# Schematic.net
KiCad netlist of a schematic drawn in Altium Designer
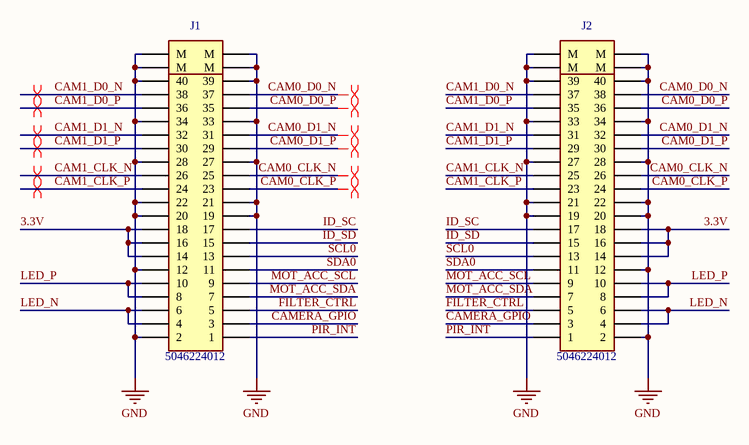
[diagram p0: Schematic.SchDoc]

(export (version "E")
  (design (tool "Eeschema 10.0.6"))
  (components
    (comp (ref "J1")
      (value "5046224012")
      (footprint "MOLEX 5046224012")
      (description "SMT 2x20 0.35mm Straight 50V 0.3A")
      (fields (field (name "02 MPN") "5046224012"))
      (libsource (lib "MS_Altium_Lib") (part "CONNECTOR 2X22 4MNT ODDEVEN"))
    )
    (comp (ref "J2")
      (value "5046224012")
      (footprint "MOLEX 5046224012")
      (description "SMT 2x20 0.35mm Straight 50V 0.3A")
      (fields (field (name "02 MPN") "5046224012"))
      (libsource (lib "") (part "CONNECTOR 2X22 4MNT ODDEVEN_1"))
    )
  )
  (nets
    (net (code "1") (name "/3.3V") (class "Default")
      (node (ref "J1") (pin "14") (pinfunction "14_14") (pintype "passive"))
      (node (ref "J1") (pin "16") (pinfunction "16_16") (pintype "passive"))
      (node (ref "J1") (pin "18") (pinfunction "18_18") (pintype "passive"))
      (node (ref "J2") (pin "14") (pinfunction "14_14") (pintype "passive"))
      (node (ref "J2") (pin "16") (pinfunction "16_16") (pintype "passive"))
      (node (ref "J2") (pin "18") (pinfunction "18_18") (pintype "passive"))
    )
    (net (code "2") (name "/CAM0_CLK_N") (class "Default")
      (node (ref "J1") (pin "25") (pinfunction "25_25") (pintype "passive"))
      (node (ref "J2") (pin "26") (pinfunction "26_26") (pintype "passive"))
    )
    (net (code "3") (name "/CAM0_CLK_P") (class "Default")
      (node (ref "J1") (pin "23") (pinfunction "23_23") (pintype "passive"))
      (node (ref "J2") (pin "24") (pinfunction "24_24") (pintype "passive"))
    )
    (net (code "4") (name "/CAM0_D0_N") (class "Default")
      (node (ref "J1") (pin "37") (pinfunction "37_37") (pintype "passive"))
      (node (ref "J2") (pin "38") (pinfunction "38_38") (pintype "passive"))
    )
    (net (code "5") (name "/CAM0_D0_P") (class "Default")
      (node (ref "J1") (pin "35") (pinfunction "35_35") (pintype "passive"))
      (node (ref "J2") (pin "36") (pinfunction "36_36") (pintype "passive"))
    )
    (net (code "6") (name "/CAM0_D1_N") (class "Default")
      (node (ref "J1") (pin "31") (pinfunction "31_31") (pintype "passive"))
      (node (ref "J2") (pin "32") (pinfunction "32_32") (pintype "passive"))
    )
    (net (code "7") (name "/CAM0_D1_P") (class "Default")
      (node (ref "J1") (pin "29") (pinfunction "29_29") (pintype "passive"))
      (node (ref "J2") (pin "30") (pinfunction "30_30") (pintype "passive"))
    )
    (net (code "8") (name "/CAM1_CLK_N") (class "Default")
      (node (ref "J1") (pin "26") (pinfunction "26_26") (pintype "passive"))
      (node (ref "J2") (pin "25") (pinfunction "25_25") (pintype "passive"))
    )
    (net (code "9") (name "/CAM1_CLK_P") (class "Default")
      (node (ref "J1") (pin "24") (pinfunction "24_24") (pintype "passive"))
      (node (ref "J2") (pin "23") (pinfunction "23_23") (pintype "passive"))
    )
    (net (code "10") (name "/CAM1_D0_N") (class "Default")
      (node (ref "J1") (pin "38") (pinfunction "38_38") (pintype "passive"))
      (node (ref "J2") (pin "37") (pinfunction "37_37") (pintype "passive"))
    )
    (net (code "11") (name "/CAM1_D0_P") (class "Default")
      (node (ref "J1") (pin "36") (pinfunction "36_36") (pintype "passive"))
      (node (ref "J2") (pin "35") (pinfunction "35_35") (pintype "passive"))
    )
    (net (code "12") (name "/CAM1_D1_N") (class "Default")
      (node (ref "J1") (pin "32") (pinfunction "32_32") (pintype "passive"))
      (node (ref "J2") (pin "31") (pinfunction "31_31") (pintype "passive"))
    )
    (net (code "13") (name "/CAM1_D1_P") (class "Default")
      (node (ref "J1") (pin "30") (pinfunction "30_30") (pintype "passive"))
      (node (ref "J2") (pin "29") (pinfunction "29_29") (pintype "passive"))
    )
    (net (code "14") (name "/CAMERA_GPIO") (class "Default")
      (node (ref "J1") (pin "3") (pinfunction "3_3") (pintype "passive"))
      (node (ref "J2") (pin "3") (pinfunction "3_3") (pintype "passive"))
    )
    (net (code "15") (name "/FILTER_CTRL") (class "Default")
      (node (ref "J1") (pin "5") (pinfunction "5_5") (pintype "passive"))
      (node (ref "J2") (pin "5") (pinfunction "5_5") (pintype "passive"))
    )
    (net (code "16") (name "/ID_SC") (class "Default")
      (node (ref "J1") (pin "17") (pinfunction "17_17") (pintype "passive"))
      (node (ref "J2") (pin "17") (pinfunction "17_17") (pintype "passive"))
    )
    (net (code "17") (name "/ID_SD") (class "Default")
      (node (ref "J1") (pin "15") (pinfunction "15_15") (pintype "passive"))
      (node (ref "J2") (pin "15") (pinfunction "15_15") (pintype "passive"))
    )
    (net (code "18") (name "/LED_N") (class "Default")
      (node (ref "J1") (pin "4") (pinfunction "4_4") (pintype "passive"))
      (node (ref "J1") (pin "6") (pinfunction "6_6") (pintype "passive"))
      (node (ref "J2") (pin "4") (pinfunction "4_4") (pintype "passive"))
      (node (ref "J2") (pin "6") (pinfunction "6_6") (pintype "passive"))
    )
    (net (code "19") (name "/LED_P") (class "Default")
      (node (ref "J1") (pin "10") (pinfunction "10_10") (pintype "passive"))
      (node (ref "J1") (pin "8") (pinfunction "8_8") (pintype "passive"))
      (node (ref "J2") (pin "10") (pinfunction "10_10") (pintype "passive"))
      (node (ref "J2") (pin "8") (pinfunction "8_8") (pintype "passive"))
    )
    (net (code "20") (name "/MOT_ACC_SCL") (class "Default")
      (node (ref "J1") (pin "9") (pinfunction "9_9") (pintype "passive"))
      (node (ref "J2") (pin "9") (pinfunction "9_9") (pintype "passive"))
    )
    (net (code "21") (name "/MOT_ACC_SDA") (class "Default")
      (node (ref "J1") (pin "7") (pinfunction "7_7") (pintype "passive"))
      (node (ref "J2") (pin "7") (pinfunction "7_7") (pintype "passive"))
    )
    (net (code "22") (name "/PIR_INT") (class "Default")
      (node (ref "J1") (pin "1") (pinfunction "1_1") (pintype "passive"))
      (node (ref "J2") (pin "1") (pinfunction "1_1") (pintype "passive"))
    )
    (net (code "23") (name "/SCL0") (class "Default")
      (node (ref "J1") (pin "13") (pinfunction "13_13") (pintype "passive"))
      (node (ref "J2") (pin "13") (pinfunction "13_13") (pintype "passive"))
    )
    (net (code "24") (name "/SDA0") (class "Default")
      (node (ref "J1") (pin "11") (pinfunction "11_11") (pintype "passive"))
      (node (ref "J2") (pin "11") (pinfunction "11_11") (pintype "passive"))
    )
    (net (code "25") (name "GND") (class "Default")
      (node (ref "J1") (pin "12") (pinfunction "12_12") (pintype "passive"))
      (node (ref "J1") (pin "19") (pinfunction "19_19") (pintype "passive"))
      (node (ref "J1") (pin "2") (pinfunction "2_2") (pintype "passive"))
      (node (ref "J1") (pin "20") (pinfunction "20_20") (pintype "passive"))
      (node (ref "J1") (pin "21") (pinfunction "21_21") (pintype "passive"))
      (node (ref "J1") (pin "22") (pinfunction "22_22") (pintype "passive"))
      (node (ref "J1") (pin "27") (pinfunction "27_27") (pintype "passive"))
      (node (ref "J1") (pin "28") (pinfunction "28_28") (pintype "passive"))
      (node (ref "J1") (pin "33") (pinfunction "33_33") (pintype "passive"))
      (node (ref "J1") (pin "34") (pinfunction "34_34") (pintype "passive"))
      (node (ref "J1") (pin "39") (pinfunction "39_39") (pintype "passive"))
      (node (ref "J1") (pin "40") (pinfunction "40_40") (pintype "passive"))
      (node (ref "J1") (pin "MNT1") (pinfunction "M_MNT1") (pintype "passive"))
      (node (ref "J1") (pin "MNT2") (pinfunction "M_MNT2") (pintype "passive"))
      (node (ref "J1") (pin "MNT3") (pinfunction "M_MNT3") (pintype "passive"))
      (node (ref "J1") (pin "MNT4") (pinfunction "M_MNT4") (pintype "passive"))
      (node (ref "J2") (pin "12") (pinfunction "12_12") (pintype "passive"))
      (node (ref "J2") (pin "19") (pinfunction "19_19") (pintype "passive"))
      (node (ref "J2") (pin "2") (pinfunction "2_2") (pintype "passive"))
      (node (ref "J2") (pin "20") (pinfunction "20_20") (pintype "passive"))
      (node (ref "J2") (pin "21") (pinfunction "21_21") (pintype "passive"))
      (node (ref "J2") (pin "22") (pinfunction "22_22") (pintype "passive"))
      (node (ref "J2") (pin "27") (pinfunction "27_27") (pintype "passive"))
      (node (ref "J2") (pin "28") (pinfunction "28_28") (pintype "passive"))
      (node (ref "J2") (pin "33") (pinfunction "33_33") (pintype "passive"))
      (node (ref "J2") (pin "34") (pinfunction "34_34") (pintype "passive"))
      (node (ref "J2") (pin "39") (pinfunction "39_39") (pintype "passive"))
      (node (ref "J2") (pin "40") (pinfunction "40_40") (pintype "passive"))
      (node (ref "J2") (pin "MNT1") (pinfunction "M_MNT1") (pintype "passive"))
      (node (ref "J2") (pin "MNT2") (pinfunction "M_MNT2") (pintype "passive"))
      (node (ref "J2") (pin "MNT3") (pinfunction "M_MNT3") (pintype "passive"))
      (node (ref "J2") (pin "MNT4") (pinfunction "M_MNT4") (pintype "passive"))
    )
  )
)
